# HMI_LEDs.net
KiCad netlist of a schematic drawn in Altium Designer
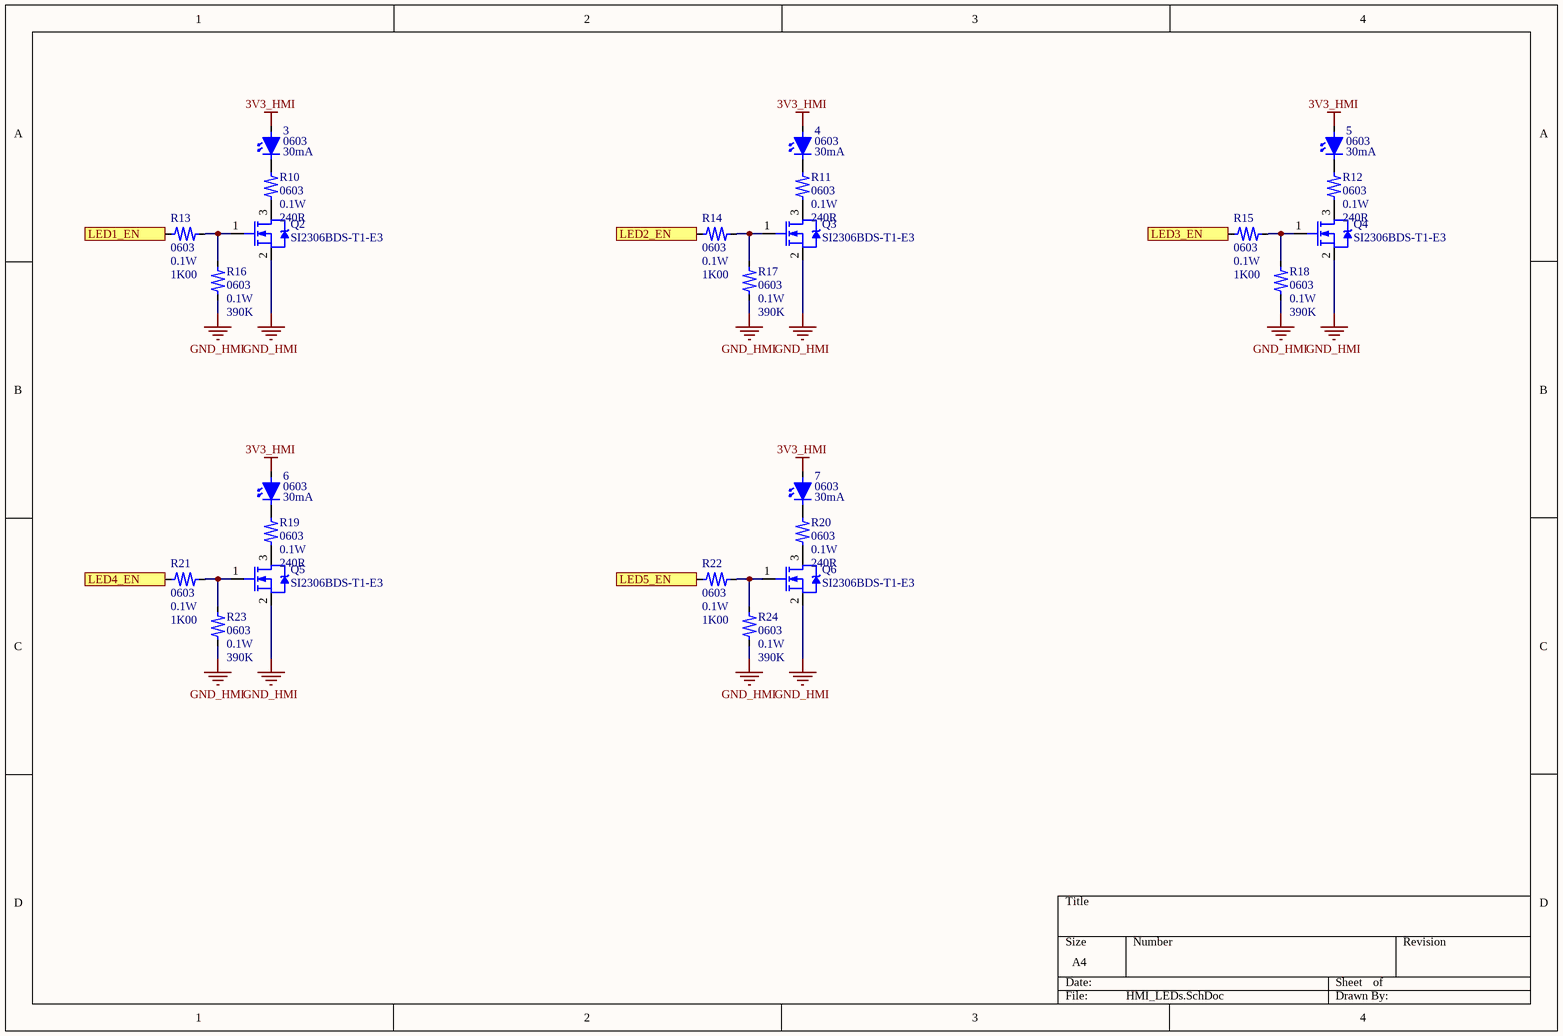
[diagram p0: HMI_LEDs.SchDoc]

(export (version "E")
  (design (tool "Eeschema 10.0.6"))
  (components
    (comp (ref "3")
      (value "0603")
      (footprint "LED_0603")
      (fields
        (field (name "PART NUMBER") "FYLS-0603UGC")
        (field (name "TOLERANCE") "5%")
        (field (name "RATING") "30mA")
      )
      (libsource (lib "Components") (part "Diode_LED"))
    )
    (comp (ref "4")
      (value "0603")
      (footprint "LED_0603")
      (fields
        (field (name "PART NUMBER") "FYLS-0603UGC")
        (field (name "TOLERANCE") "5%")
        (field (name "RATING") "30mA")
      )
      (libsource (lib "Components") (part "Diode_LED"))
    )
    (comp (ref "5")
      (value "0603")
      (footprint "LED_0603")
      (fields
        (field (name "PART NUMBER") "FYLS-0603UGC")
        (field (name "TOLERANCE") "5%")
        (field (name "RATING") "30mA")
      )
      (libsource (lib "Components") (part "Diode_LED"))
    )
    (comp (ref "6")
      (value "0603")
      (footprint "LED_0603")
      (fields
        (field (name "PART NUMBER") "FYLS-0603UGC")
        (field (name "TOLERANCE") "5%")
        (field (name "RATING") "30mA")
      )
      (libsource (lib "Components") (part "Diode_LED"))
    )
    (comp (ref "7")
      (value "0603")
      (footprint "LED_0603")
      (fields
        (field (name "PART NUMBER") "FYLS-0603UGC")
        (field (name "TOLERANCE") "5%")
        (field (name "RATING") "30mA")
      )
      (libsource (lib "Components") (part "Diode_LED"))
    )
    (comp (ref "Q2")
      (value "SI2306BDS-T1-E3")
      (footprint "SOT-23-3")
      (description "N-Channel Power MOSFET")
      (libsource (lib "Components") (part "Transistor_N-FET"))
    )
    (comp (ref "Q3")
      (value "SI2306BDS-T1-E3")
      (footprint "SOT-23-3")
      (description "N-Channel Power MOSFET")
      (libsource (lib "Components") (part "Transistor_N-FET"))
    )
    (comp (ref "Q4")
      (value "SI2306BDS-T1-E3")
      (footprint "SOT-23-3")
      (description "N-Channel Power MOSFET")
      (libsource (lib "Components") (part "Transistor_N-FET"))
    )
    (comp (ref "Q5")
      (value "SI2306BDS-T1-E3")
      (footprint "SOT-23-3")
      (description "N-Channel Power MOSFET")
      (libsource (lib "Components") (part "Transistor_N-FET"))
    )
    (comp (ref "Q6")
      (value "SI2306BDS-T1-E3")
      (footprint "SOT-23-3")
      (description "N-Channel Power MOSFET")
      (libsource (lib "Components") (part "Transistor_N-FET"))
    )
    (comp (ref "R10")
      (value "0603")
      (footprint "R_0603")
      (fields
        (field (name "TOLERANCE") "5%")
        (field (name "PART NUMBER") "CR-03JL7--240R")
        (field (name "RATING") "0.1W")
        (field (name "ALTIUM_VALUE") "240R")
        (field (name "NI PART NUMBER") "612640-01")
      )
      (libsource (lib "Components") (part "Resistor_Chip"))
    )
    (comp (ref "R11")
      (value "0603")
      (footprint "R_0603")
      (fields
        (field (name "TOLERANCE") "5%")
        (field (name "PART NUMBER") "CR-03JL7--240R")
        (field (name "RATING") "0.1W")
        (field (name "ALTIUM_VALUE") "240R")
        (field (name "NI PART NUMBER") "612640-01")
      )
      (libsource (lib "Components") (part "Resistor_Chip"))
    )
    (comp (ref "R12")
      (value "0603")
      (footprint "R_0603")
      (fields
        (field (name "TOLERANCE") "5%")
        (field (name "PART NUMBER") "CR-03JL7--240R")
        (field (name "RATING") "0.1W")
        (field (name "ALTIUM_VALUE") "240R")
        (field (name "NI PART NUMBER") "612640-01")
      )
      (libsource (lib "Components") (part "Resistor_Chip"))
    )
    (comp (ref "R13")
      (value "0603")
      (footprint "R_0603")
      (fields
        (field (name "TOLERANCE") "1%")
        (field (name "PART NUMBER") "CR-03FL7----1K")
        (field (name "RATING") "0.1W")
        (field (name "ALTIUM_VALUE") "1K00")
        (field (name "NI PART NUMBER") "713776-01")
      )
      (libsource (lib "Components") (part "Resistor_Chip"))
    )
    (comp (ref "R14")
      (value "0603")
      (footprint "R_0603")
      (fields
        (field (name "TOLERANCE") "1%")
        (field (name "PART NUMBER") "CR-03FL7----1K")
        (field (name "RATING") "0.1W")
        (field (name "ALTIUM_VALUE") "1K00")
        (field (name "NI PART NUMBER") "713776-01")
      )
      (libsource (lib "Components") (part "Resistor_Chip"))
    )
    (comp (ref "R15")
      (value "0603")
      (footprint "R_0603")
      (fields
        (field (name "TOLERANCE") "1%")
        (field (name "PART NUMBER") "CR-03FL7----1K")
        (field (name "RATING") "0.1W")
        (field (name "ALTIUM_VALUE") "1K00")
        (field (name "NI PART NUMBER") "713776-01")
      )
      (libsource (lib "Components") (part "Resistor_Chip"))
    )
    (comp (ref "R16")
      (value "0603")
      (footprint "R_0603")
      (fields
        (field (name "TOLERANCE") "1%")
        (field (name "PART NUMBER") "CR-03FL7--390K")
        (field (name "RATING") "0.1W")
        (field (name "ALTIUM_VALUE") "390K")
      )
      (libsource (lib "Components") (part "Resistor_Chip"))
    )
    (comp (ref "R17")
      (value "0603")
      (footprint "R_0603")
      (fields
        (field (name "TOLERANCE") "1%")
        (field (name "PART NUMBER") "CR-03FL7--390K")
        (field (name "RATING") "0.1W")
        (field (name "ALTIUM_VALUE") "390K")
      )
      (libsource (lib "Components") (part "Resistor_Chip"))
    )
    (comp (ref "R18")
      (value "0603")
      (footprint "R_0603")
      (fields
        (field (name "TOLERANCE") "1%")
        (field (name "PART NUMBER") "CR-03FL7--390K")
        (field (name "RATING") "0.1W")
        (field (name "ALTIUM_VALUE") "390K")
      )
      (libsource (lib "Components") (part "Resistor_Chip"))
    )
    (comp (ref "R19")
      (value "0603")
      (footprint "R_0603")
      (fields
        (field (name "TOLERANCE") "5%")
        (field (name "PART NUMBER") "CR-03JL7--240R")
        (field (name "RATING") "0.1W")
        (field (name "ALTIUM_VALUE") "240R")
        (field (name "NI PART NUMBER") "612640-01")
      )
      (libsource (lib "Components") (part "Resistor_Chip"))
    )
    (comp (ref "R20")
      (value "0603")
      (footprint "R_0603")
      (fields
        (field (name "TOLERANCE") "5%")
        (field (name "PART NUMBER") "CR-03JL7--240R")
        (field (name "RATING") "0.1W")
        (field (name "ALTIUM_VALUE") "240R")
        (field (name "NI PART NUMBER") "612640-01")
      )
      (libsource (lib "Components") (part "Resistor_Chip"))
    )
    (comp (ref "R21")
      (value "0603")
      (footprint "R_0603")
      (fields
        (field (name "TOLERANCE") "1%")
        (field (name "PART NUMBER") "CR-03FL7----1K")
        (field (name "RATING") "0.1W")
        (field (name "ALTIUM_VALUE") "1K00")
        (field (name "NI PART NUMBER") "713776-01")
      )
      (libsource (lib "Components") (part "Resistor_Chip"))
    )
    (comp (ref "R22")
      (value "0603")
      (footprint "R_0603")
      (fields
        (field (name "TOLERANCE") "1%")
        (field (name "PART NUMBER") "CR-03FL7----1K")
        (field (name "RATING") "0.1W")
        (field (name "ALTIUM_VALUE") "1K00")
        (field (name "NI PART NUMBER") "713776-01")
      )
      (libsource (lib "Components") (part "Resistor_Chip"))
    )
    (comp (ref "R23")
      (value "0603")
      (footprint "R_0603")
      (fields
        (field (name "TOLERANCE") "1%")
        (field (name "PART NUMBER") "CR-03FL7--390K")
        (field (name "RATING") "0.1W")
        (field (name "ALTIUM_VALUE") "390K")
      )
      (libsource (lib "Components") (part "Resistor_Chip"))
    )
    (comp (ref "R24")
      (value "0603")
      (footprint "R_0603")
      (fields
        (field (name "TOLERANCE") "1%")
        (field (name "PART NUMBER") "CR-03FL7--390K")
        (field (name "RATING") "0.1W")
        (field (name "ALTIUM_VALUE") "390K")
      )
      (libsource (lib "Components") (part "Resistor_Chip"))
    )
  )
  (nets
    (net (code "1") (name "/LED1_EN") (class "Default")
      (node (ref "R13") (pin "1") (pinfunction "R1_1") (pintype "passive"))
    )
    (net (code "2") (name "/LED2_EN") (class "Default")
      (node (ref "R14") (pin "1") (pinfunction "R1_1") (pintype "passive"))
    )
    (net (code "3") (name "/LED3_EN") (class "Default")
      (node (ref "R15") (pin "1") (pinfunction "R1_1") (pintype "passive"))
    )
    (net (code "4") (name "/LED4_EN") (class "Default")
      (node (ref "R21") (pin "1") (pinfunction "R1_1") (pintype "passive"))
    )
    (net (code "5") (name "/LED5_EN") (class "Default")
      (node (ref "R22") (pin "1") (pinfunction "R1_1") (pintype "passive"))
    )
    (net (code "6") (name "3V3_HMI") (class "Default")
      (node (ref "3") (pin "2") (pinfunction "DA_2") (pintype "passive"))
      (node (ref "4") (pin "2") (pinfunction "DA_2") (pintype "passive"))
      (node (ref "5") (pin "2") (pinfunction "DA_2") (pintype "passive"))
      (node (ref "6") (pin "2") (pinfunction "DA_2") (pintype "passive"))
      (node (ref "7") (pin "2") (pinfunction "DA_2") (pintype "passive"))
    )
    (net (code "7") (name "GND_HMI") (class "Default")
      (node (ref "Q2") (pin "2") (pinfunction "S_2") (pintype "passive"))
      (node (ref "Q3") (pin "2") (pinfunction "S_2") (pintype "passive"))
      (node (ref "Q4") (pin "2") (pinfunction "S_2") (pintype "passive"))
      (node (ref "Q5") (pin "2") (pinfunction "S_2") (pintype "passive"))
      (node (ref "Q6") (pin "2") (pinfunction "S_2") (pintype "passive"))
      (node (ref "R16") (pin "1") (pinfunction "R1_1") (pintype "passive"))
      (node (ref "R17") (pin "1") (pinfunction "R1_1") (pintype "passive"))
      (node (ref "R18") (pin "1") (pinfunction "R1_1") (pintype "passive"))
      (node (ref "R23") (pin "1") (pinfunction "R1_1") (pintype "passive"))
      (node (ref "R24") (pin "1") (pinfunction "R1_1") (pintype "passive"))
    )
    (net (code "8") (name "Net-(3-DC)") (class "Default")
      (node (ref "3") (pin "1") (pinfunction "DC_1") (pintype "passive"))
      (node (ref "R10") (pin "2") (pinfunction "R2_2") (pintype "passive"))
    )
    (net (code "9") (name "Net-(4-DC)") (class "Default")
      (node (ref "4") (pin "1") (pinfunction "DC_1") (pintype "passive"))
      (node (ref "R11") (pin "2") (pinfunction "R2_2") (pintype "passive"))
    )
    (net (code "10") (name "Net-(5-DC)") (class "Default")
      (node (ref "5") (pin "1") (pinfunction "DC_1") (pintype "passive"))
      (node (ref "R12") (pin "2") (pinfunction "R2_2") (pintype "passive"))
    )
    (net (code "11") (name "Net-(6-DC)") (class "Default")
      (node (ref "6") (pin "1") (pinfunction "DC_1") (pintype "passive"))
      (node (ref "R19") (pin "2") (pinfunction "R2_2") (pintype "passive"))
    )
    (net (code "12") (name "Net-(7-DC)") (class "Default")
      (node (ref "7") (pin "1") (pinfunction "DC_1") (pintype "passive"))
      (node (ref "R20") (pin "2") (pinfunction "R2_2") (pintype "passive"))
    )
    (net (code "13") (name "Net-(Q2-D)") (class "Default")
      (node (ref "Q2") (pin "3") (pinfunction "D_3") (pintype "passive"))
      (node (ref "R10") (pin "1") (pinfunction "R1_1") (pintype "passive"))
    )
    (net (code "14") (name "Net-(Q2-G)") (class "Default")
      (node (ref "Q2") (pin "1") (pinfunction "G_1") (pintype "passive"))
      (node (ref "R13") (pin "2") (pinfunction "R2_2") (pintype "passive"))
      (node (ref "R16") (pin "2") (pinfunction "R2_2") (pintype "passive"))
    )
    (net (code "15") (name "Net-(Q3-D)") (class "Default")
      (node (ref "Q3") (pin "3") (pinfunction "D_3") (pintype "passive"))
      (node (ref "R11") (pin "1") (pinfunction "R1_1") (pintype "passive"))
    )
    (net (code "16") (name "Net-(Q3-G)") (class "Default")
      (node (ref "Q3") (pin "1") (pinfunction "G_1") (pintype "passive"))
      (node (ref "R14") (pin "2") (pinfunction "R2_2") (pintype "passive"))
      (node (ref "R17") (pin "2") (pinfunction "R2_2") (pintype "passive"))
    )
    (net (code "17") (name "Net-(Q4-D)") (class "Default")
      (node (ref "Q4") (pin "3") (pinfunction "D_3") (pintype "passive"))
      (node (ref "R12") (pin "1") (pinfunction "R1_1") (pintype "passive"))
    )
    (net (code "18") (name "Net-(Q4-G)") (class "Default")
      (node (ref "Q4") (pin "1") (pinfunction "G_1") (pintype "passive"))
      (node (ref "R15") (pin "2") (pinfunction "R2_2") (pintype "passive"))
      (node (ref "R18") (pin "2") (pinfunction "R2_2") (pintype "passive"))
    )
    (net (code "19") (name "Net-(Q5-D)") (class "Default")
      (node (ref "Q5") (pin "3") (pinfunction "D_3") (pintype "passive"))
      (node (ref "R19") (pin "1") (pinfunction "R1_1") (pintype "passive"))
    )
    (net (code "20") (name "Net-(Q5-G)") (class "Default")
      (node (ref "Q5") (pin "1") (pinfunction "G_1") (pintype "passive"))
      (node (ref "R21") (pin "2") (pinfunction "R2_2") (pintype "passive"))
      (node (ref "R23") (pin "2") (pinfunction "R2_2") (pintype "passive"))
    )
    (net (code "21") (name "Net-(Q6-D)") (class "Default")
      (node (ref "Q6") (pin "3") (pinfunction "D_3") (pintype "passive"))
      (node (ref "R20") (pin "1") (pinfunction "R1_1") (pintype "passive"))
    )
    (net (code "22") (name "Net-(Q6-G)") (class "Default")
      (node (ref "Q6") (pin "1") (pinfunction "G_1") (pintype "passive"))
      (node (ref "R22") (pin "2") (pinfunction "R2_2") (pintype "passive"))
      (node (ref "R24") (pin "2") (pinfunction "R2_2") (pintype "passive"))
    )
  )
)
